# logic.net
KiCad netlist of a schematic drawn in Altium Designer
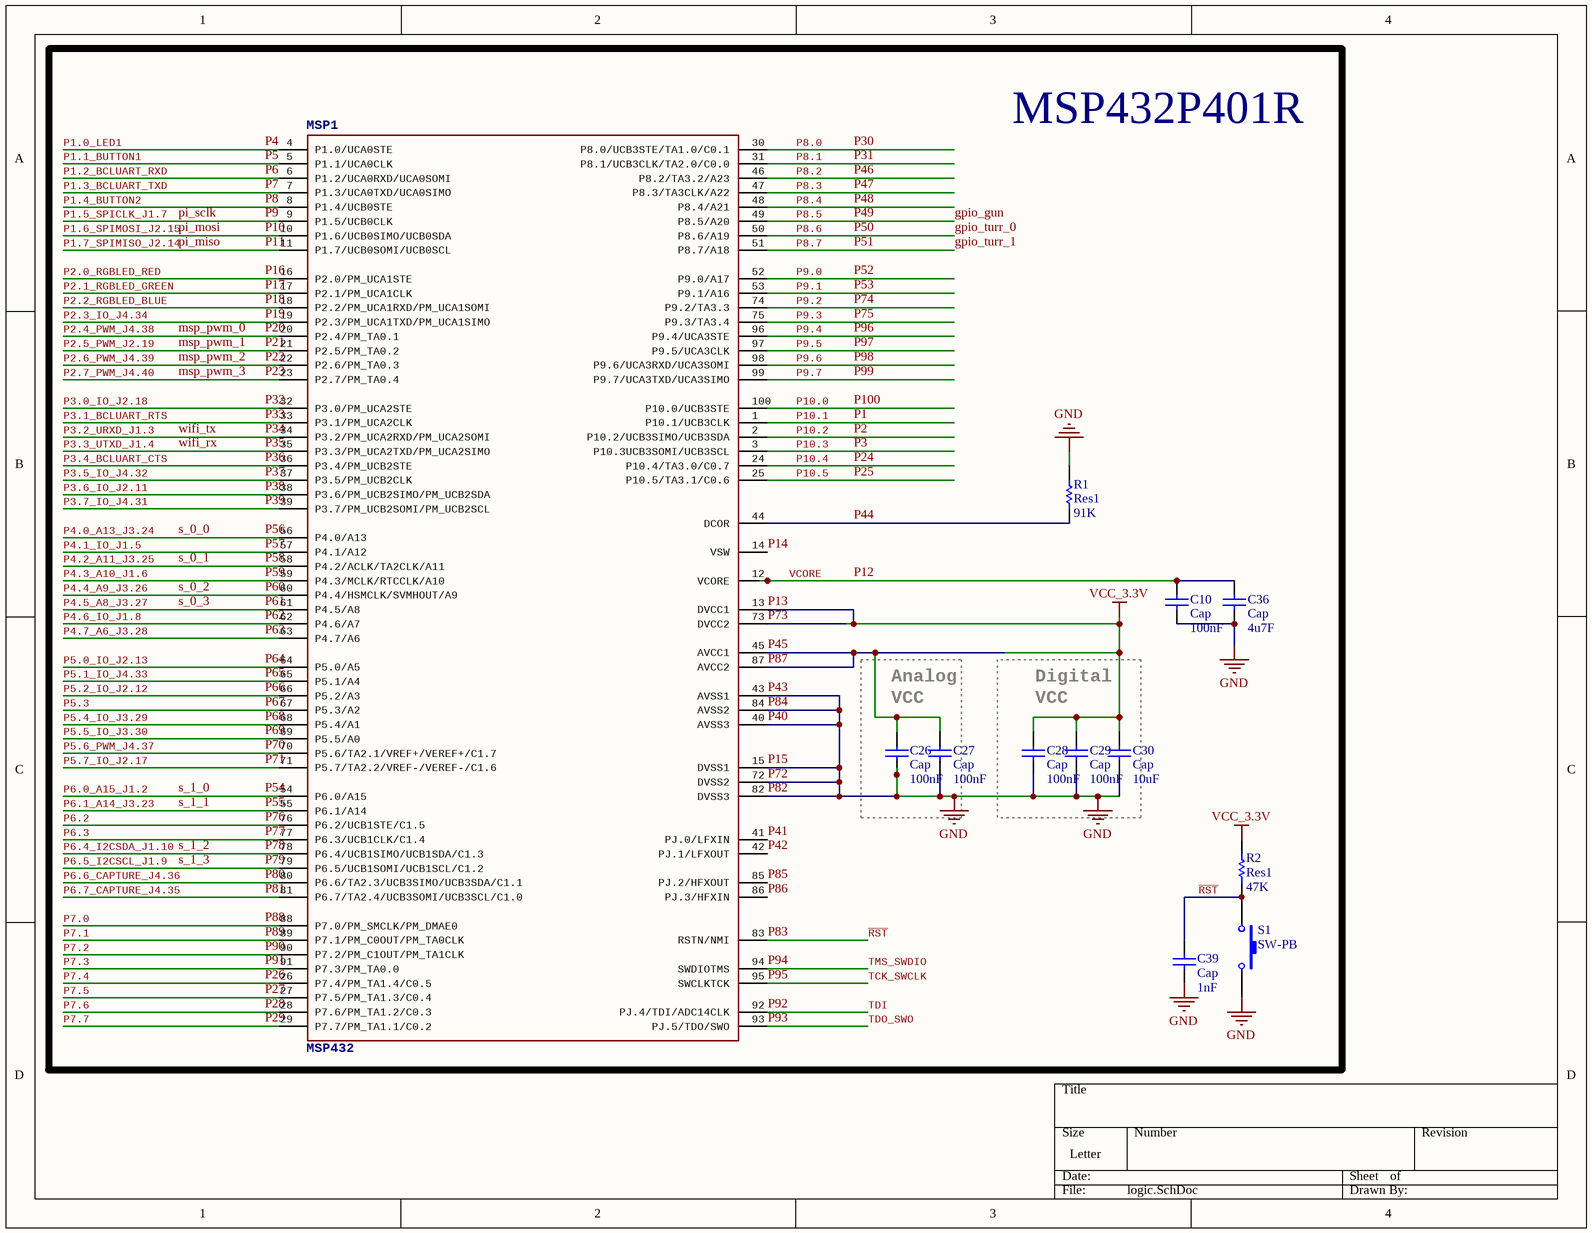
[diagram p0: logic.SchDoc]

(export (version "E")
  (design (tool "Eeschema 10.0.6"))
  (components
    (comp (ref "C10")
      (value "Cap")
      (footprint "RAD-0.1")
      (description "Capacitor")
      (fields (field (name "ALTIUM_VALUE") "100nF") (field (name "PUBLISHER") "Altium Limited"))
      (libsource (lib "Miscellaneous Devices") (part "Cap"))
    )
    (comp (ref "C26")
      (value "Cap")
      (footprint "RAD-0.1")
      (description "Capacitor")
      (fields (field (name "ALTIUM_VALUE") "100nF") (field (name "PUBLISHER") "Altium Limited"))
      (libsource (lib "Miscellaneous Devices") (part "Cap"))
    )
    (comp (ref "C27")
      (value "Cap")
      (footprint "RAD-0.1")
      (description "Capacitor")
      (fields (field (name "ALTIUM_VALUE") "100nF") (field (name "PUBLISHER") "Altium Limited"))
      (libsource (lib "Miscellaneous Devices") (part "Cap"))
    )
    (comp (ref "C28")
      (value "Cap")
      (footprint "RAD-0.1")
      (description "Capacitor")
      (fields (field (name "ALTIUM_VALUE") "100nF") (field (name "PUBLISHER") "Altium Limited"))
      (libsource (lib "Miscellaneous Devices") (part "Cap"))
    )
    (comp (ref "C29")
      (value "Cap")
      (footprint "RAD-0.1")
      (description "Capacitor")
      (fields (field (name "ALTIUM_VALUE") "100nF") (field (name "PUBLISHER") "Altium Limited"))
      (libsource (lib "Miscellaneous Devices") (part "Cap"))
    )
    (comp (ref "C30")
      (value "Cap")
      (footprint "RAD-0.1")
      (description "Capacitor")
      (fields (field (name "ALTIUM_VALUE") "10uF") (field (name "PUBLISHER") "Altium Limited"))
      (libsource (lib "Miscellaneous Devices") (part "Cap"))
    )
    (comp (ref "C36")
      (value "Cap")
      (footprint "RAD-0.1")
      (description "Capacitor")
      (fields (field (name "ALTIUM_VALUE") "4u7F") (field (name "PUBLISHER") "Altium Limited"))
      (libsource (lib "Miscellaneous Devices") (part "Cap"))
    )
    (comp (ref "C39")
      (value "Cap")
      (footprint "RAD-0.1")
      (description "Capacitor")
      (fields (field (name "ALTIUM_VALUE") "1nF") (field (name "PUBLISHER") "Altium Limited"))
      (libsource (lib "Miscellaneous Devices") (part "Cap"))
    )
    (comp (ref "MSP1") (value "MSP432") (footprint "PZ100_L") (libsource (lib "MSP-EXP432") (part "MSP432")))
    (comp (ref "R1")
      (value "Res1")
      (footprint "AXIAL-0.3")
      (description "Resistor")
      (fields (field (name "ALTIUM_VALUE") "91K") (field (name "PUBLISHER") "Altium Limited"))
      (libsource (lib "Miscellaneous Devices") (part "Res1"))
    )
    (comp (ref "R2")
      (value "Res1")
      (footprint "AXIAL-0.3")
      (description "Resistor")
      (fields (field (name "ALTIUM_VALUE") "47K") (field (name "PUBLISHER") "Altium Limited"))
      (libsource (lib "Miscellaneous Devices") (part "Res1"))
    )
    (comp (ref "S1")
      (value "SW-PB")
      (footprint "SW PB")
      (description "DIGIKEY SW400-ND")
      (fields (field (name "PUBLISHER") "Altium Limited"))
      (libsource (lib "ECE LIB new") (part "SW-PB_2"))
    )
  )
  (nets
    (net (code "1") (name "/P1") (class "Default")
      (node (ref "MSP1") (pin "1") (pinfunction "P10.1/UCB3CLK_1") (pintype "power_in"))
    )
    (net (code "2") (name "/P1.0_LED1") (class "Default")
      (node (ref "MSP1") (pin "4") (pinfunction "P1.0/UCA0STE_4") (pintype "power_in"))
    )
    (net (code "3") (name "/P1.1_BUTTON1") (class "Default")
      (node (ref "MSP1") (pin "5") (pinfunction "P1.1/UCA0CLK_5") (pintype "power_in"))
    )
    (net (code "4") (name "/P1.2_BCLUART_RXD") (class "Default")
      (node (ref "MSP1") (pin "6") (pinfunction "P1.2/UCA0RXD/UCA0SOMI_6") (pintype "power_in"))
    )
    (net (code "5") (name "/P1.3_BCLUART_TXD") (class "Default")
      (node (ref "MSP1") (pin "7") (pinfunction "P1.3/UCA0TXD/UCA0SIMO_7") (pintype "power_in"))
    )
    (net (code "6") (name "/P1.4_BUTTON2") (class "Default")
      (node (ref "MSP1") (pin "8") (pinfunction "P1.4/UCB0STE_8") (pintype "power_in"))
    )
    (net (code "7") (name "/P1.5_SPICLK_J1.7") (class "Default")
      (node (ref "MSP1") (pin "9") (pinfunction "P1.5/UCB0CLK_9") (pintype "power_in"))
    )
    (net (code "8") (name "/P1.6_SPIMOSI_J2.15") (class "Default")
      (node (ref "MSP1") (pin "10") (pinfunction "P1.6/UCB0SIMO/UCB0SDA_10") (pintype "power_in"))
    )
    (net (code "9") (name "/P1.7_SPIMISO_J2.14") (class "Default")
      (node (ref "MSP1") (pin "11") (pinfunction "P1.7/UCB0SOMI/UCB0SCL_11") (pintype "power_in"))
    )
    (net (code "10") (name "/P2.4_PWM_J4.38") (class "Default")
      (node (ref "MSP1") (pin "20") (pinfunction "P2.4/PM_TA0.1_20") (pintype "power_in"))
    )
    (net (code "11") (name "/P2.5_PWM_J2.19") (class "Default")
      (node (ref "MSP1") (pin "21") (pinfunction "P2.5/PM_TA0.2_21") (pintype "power_in"))
    )
    (net (code "12") (name "/P2.6_PWM_J4.39") (class "Default")
      (node (ref "MSP1") (pin "22") (pinfunction "P2.6/PM_TA0.3_22") (pintype "power_in"))
    )
    (net (code "13") (name "/P2.7_PWM_J4.40") (class "Default")
      (node (ref "MSP1") (pin "23") (pinfunction "P2.7/PM_TA0.4_23") (pintype "power_in"))
    )
    (net (code "14") (name "/P3.0_IO_J2.18") (class "Default")
      (node (ref "MSP1") (pin "32") (pinfunction "P3.0/PM_UCA2STE_32") (pintype "power_in"))
    )
    (net (code "15") (name "/P3.1_BCLUART_RTS") (class "Default")
      (node (ref "MSP1") (pin "33") (pinfunction "P3.1/PM_UCA2CLK_33") (pintype "power_in"))
    )
    (net (code "16") (name "/P3.2_URXD_J1.3") (class "Default")
      (node (ref "MSP1") (pin "34") (pinfunction "P3.2/PM_UCA2RXD/PM_UCA2SOMI_34") (pintype "power_in"))
    )
    (net (code "17") (name "/P3.3_UTXD_J1.4") (class "Default")
      (node (ref "MSP1") (pin "35") (pinfunction "P3.3/PM_UCA2TXD/PM_UCA2SIMO_35") (pintype "power_in"))
    )
    (net (code "18") (name "/P3.4_BCLUART_CTS") (class "Default")
      (node (ref "MSP1") (pin "36") (pinfunction "P3.4/PM_UCB2STE_36") (pintype "power_in"))
    )
    (net (code "19") (name "/P3.5_IO_J4.32") (class "Default")
      (node (ref "MSP1") (pin "37") (pinfunction "P3.5/PM_UCB2CLK_37") (pintype "power_in"))
    )
    (net (code "20") (name "/P3.6_IO_J2.11") (class "Default")
      (node (ref "MSP1") (pin "38") (pinfunction "P3.6/PM_UCB2SIMO/PM_UCB2SDA_38") (pintype "power_in"))
    )
    (net (code "21") (name "/P3.7_IO_J4.31") (class "Default")
      (node (ref "MSP1") (pin "39") (pinfunction "P3.7/PM_UCB2SOMI/PM_UCB2SCL_39") (pintype "power_in"))
    )
    (net (code "22") (name "/P4.0_A13_J3.24") (class "Default")
      (node (ref "MSP1") (pin "56") (pinfunction "P4.0/A13_56") (pintype "power_in"))
    )
    (net (code "23") (name "/P4.1_IO_J1.5") (class "Default")
      (node (ref "MSP1") (pin "57") (pinfunction "P4.1/A12_57") (pintype "power_in"))
    )
    (net (code "24") (name "/P4.2_A11_J3.25") (class "Default")
      (node (ref "MSP1") (pin "58") (pinfunction "P4.2/ACLK/TA2CLK/A11_58") (pintype "power_in"))
    )
    (net (code "25") (name "/P4.3_A10_J1.6") (class "Default")
      (node (ref "MSP1") (pin "59") (pinfunction "P4.3/MCLK/RTCCLK/A10_59") (pintype "power_in"))
    )
    (net (code "26") (name "/P4.4_A9_J3.26") (class "Default")
      (node (ref "MSP1") (pin "60") (pinfunction "P4.4/HSMCLK/SVMHOUT/A9_60") (pintype "power_in"))
    )
    (net (code "27") (name "/P4.5_A8_J3.27") (class "Default")
      (node (ref "MSP1") (pin "61") (pinfunction "P4.5/A8_61") (pintype "power_in"))
    )
    (net (code "28") (name "/P4.6_IO_J1.8") (class "Default")
      (node (ref "MSP1") (pin "62") (pinfunction "P4.6/A7_62") (pintype "power_in"))
    )
    (net (code "29") (name "/P4.7_A6_J3.28") (class "Default")
      (node (ref "MSP1") (pin "63") (pinfunction "P4.7/A6_63") (pintype "power_in"))
    )
    (net (code "30") (name "/P5.0_IO_J2.13") (class "Default")
      (node (ref "MSP1") (pin "64") (pinfunction "P5.0/A5_64") (pintype "power_in"))
    )
    (net (code "31") (name "/P5.1_IO_J4.33") (class "Default")
      (node (ref "MSP1") (pin "65") (pinfunction "P5.1/A4_65") (pintype "power_in"))
    )
    (net (code "32") (name "/P5.2_IO_J2.12") (class "Default")
      (node (ref "MSP1") (pin "66") (pinfunction "P5.2/A3_66") (pintype "power_in"))
    )
    (net (code "33") (name "/P5.3") (class "Default")
      (node (ref "MSP1") (pin "67") (pinfunction "P5.3/A2_67") (pintype "power_in"))
    )
    (net (code "34") (name "/P5.4_IO_J3.29") (class "Default")
      (node (ref "MSP1") (pin "68") (pinfunction "P5.4/A1_68") (pintype "power_in"))
    )
    (net (code "35") (name "/P5.5_IO_J3.30") (class "Default")
      (node (ref "MSP1") (pin "69") (pinfunction "P5.5/A0_69") (pintype "power_in"))
    )
    (net (code "36") (name "/P5.6_PWM_J4.37") (class "Default")
      (node (ref "MSP1") (pin "70") (pinfunction "P5.6/TA2.1/VREF+/VEREF+/C1.7_70") (pintype "power_in"))
    )
    (net (code "37") (name "/P5.7_IO_J2.17") (class "Default")
      (node (ref "MSP1") (pin "71") (pinfunction "P5.7/TA2.2/VREF-/VEREF-/C1.6_71") (pintype "power_in"))
    )
    (net (code "38") (name "/P6.2") (class "Default")
      (node (ref "MSP1") (pin "76") (pinfunction "P6.2/UCB1STE/C1.5_76") (pintype "power_in"))
    )
    (net (code "39") (name "/P6.3") (class "Default")
      (node (ref "MSP1") (pin "77") (pinfunction "P6.3/UCB1CLK/C1.4_77") (pintype "power_in"))
    )
    (net (code "40") (name "/P6.4_I2CSDA_J1.10") (class "Default")
      (node (ref "MSP1") (pin "78") (pinfunction "P6.4/UCB1SIMO/UCB1SDA/C1.3_78") (pintype "power_in"))
    )
    (net (code "41") (name "/P6.5_I2CSCL_J1.9") (class "Default")
      (node (ref "MSP1") (pin "79") (pinfunction "P6.5/UCB1SOMI/UCB1SCL/C1.2_79") (pintype "power_in"))
    )
    (net (code "42") (name "/P6.6_CAPTURE_J4.36") (class "Default")
      (node (ref "MSP1") (pin "80") (pinfunction "P6.6/TA2.3/UCB3SIMO/UCB3SDA/C1.1_80") (pintype "power_in"))
    )
    (net (code "43") (name "/P6.7_CAPTURE_J4.35") (class "Default")
      (node (ref "MSP1") (pin "81") (pinfunction "P6.7/TA2.4/UCB3SOMI/UCB3SCL/C1.0_81") (pintype "power_in"))
    )
    (net (code "44") (name "/P7.0") (class "Default")
      (node (ref "MSP1") (pin "88") (pinfunction "P7.0/PM_SMCLK/PM_DMAE0_88") (pintype "power_in"))
    )
    (net (code "45") (name "/P7.1") (class "Default")
      (node (ref "MSP1") (pin "89") (pinfunction "P7.1/PM_C0OUT/PM_TA0CLK_89") (pintype "power_in"))
    )
    (net (code "46") (name "/P7.2") (class "Default")
      (node (ref "MSP1") (pin "90") (pinfunction "P7.2/PM_C1OUT/PM_TA1CLK_90") (pintype "power_in"))
    )
    (net (code "47") (name "/P7.3") (class "Default")
      (node (ref "MSP1") (pin "91") (pinfunction "P7.3/PM_TA0.0_91") (pintype "power_in"))
    )
    (net (code "48") (name "/P9.4") (class "Default")
      (node (ref "MSP1") (pin "96") (pinfunction "P9.4/UCA3STE_96") (pintype "power_in"))
    )
    (net (code "49") (name "/P9.5") (class "Default")
      (node (ref "MSP1") (pin "97") (pinfunction "P9.5/UCA3CLK_97") (pintype "power_in"))
    )
    (net (code "50") (name "/P9.6") (class "Default")
      (node (ref "MSP1") (pin "98") (pinfunction "P9.6/UCA3RXD/UCA3SOMI_98") (pintype "power_in"))
    )
    (net (code "51") (name "/P9.7") (class "Default")
      (node (ref "MSP1") (pin "99") (pinfunction "P9.7/UCA3TXD/UCA3SIMO_99") (pintype "power_in"))
    )
    (net (code "52") (name "/P10.0") (class "Default")
      (node (ref "MSP1") (pin "100") (pinfunction "P10.0/UCB3STE_100") (pintype "power_in"))
    )
    (net (code "53") (name "/P10.2") (class "Default")
      (node (ref "MSP1") (pin "2") (pinfunction "P10.2/UCB3SIMO/UCB3SDA_2") (pintype "power_in"))
    )
    (net (code "54") (name "/P10.3") (class "Default")
      (node (ref "MSP1") (pin "3") (pinfunction "P10.3UCB3SOMI/UCB3SCL_3") (pintype "power_in"))
    )
    (net (code "55") (name "/P10.4") (class "Default")
      (node (ref "MSP1") (pin "24") (pinfunction "P10.4/TA3.0/C0.7_24") (pintype "power_in"))
    )
    (net (code "56") (name "/P10.5") (class "Default")
      (node (ref "MSP1") (pin "25") (pinfunction "P10.5/TA3.1/C0.6_25") (pintype "power_in"))
    )
    (net (code "57") (name "/P12") (class "Default")
      (node (ref "C10") (pin "2") (pinfunction "2_2") (pintype "passive"))
      (node (ref "C36") (pin "2") (pinfunction "2_2") (pintype "passive"))
      (node (ref "MSP1") (pin "12") (pinfunction "VCORE_12") (pintype "power_in"))
    )
    (net (code "58") (name "/P14") (class "Default")
      (node (ref "MSP1") (pin "14") (pinfunction "VSW_14") (pintype "power_in"))
    )
    (net (code "59") (name "/P16") (class "Default")
      (node (ref "MSP1") (pin "16") (pinfunction "P2.0/PM_UCA1STE_16") (pintype "power_in"))
    )
    (net (code "60") (name "/P17") (class "Default")
      (node (ref "MSP1") (pin "17") (pinfunction "P2.1/PM_UCA1CLK_17") (pintype "power_in"))
    )
    (net (code "61") (name "/P18") (class "Default")
      (node (ref "MSP1") (pin "18") (pinfunction "P2.2/PM_UCA1RXD/PM_UCA1SOMI_18") (pintype "power_in"))
    )
    (net (code "62") (name "/P19") (class "Default")
      (node (ref "MSP1") (pin "19") (pinfunction "P2.3/PM_UCA1TXD/PM_UCA1SIMO_19") (pintype "power_in"))
    )
    (net (code "63") (name "/P26") (class "Default")
      (node (ref "MSP1") (pin "26") (pinfunction "P7.4/PM_TA1.4/C0.5_26") (pintype "power_in"))
    )
    (net (code "64") (name "/P27") (class "Default")
      (node (ref "MSP1") (pin "27") (pinfunction "P7.5/PM_TA1.3/C0.4_27") (pintype "power_in"))
    )
    (net (code "65") (name "/P28") (class "Default")
      (node (ref "MSP1") (pin "28") (pinfunction "P7.6/PM_TA1.2/C0.3_28") (pintype "power_in"))
    )
    (net (code "66") (name "/P29") (class "Default")
      (node (ref "MSP1") (pin "29") (pinfunction "P7.7/PM_TA1.1/C0.2_29") (pintype "power_in"))
    )
    (net (code "67") (name "/P30") (class "Default")
      (node (ref "MSP1") (pin "30") (pinfunction "P8.0/UCB3STE/TA1.0/C0.1_30") (pintype "power_in"))
    )
    (net (code "68") (name "/P31") (class "Default")
      (node (ref "MSP1") (pin "31") (pinfunction "P8.1/UCB3CLK/TA2.0/C0.0_31") (pintype "power_in"))
    )
    (net (code "69") (name "/P41") (class "Default")
      (node (ref "MSP1") (pin "41") (pinfunction "PJ.0/LFXIN_41") (pintype "power_in"))
    )
    (net (code "70") (name "/P42") (class "Default")
      (node (ref "MSP1") (pin "42") (pinfunction "PJ.1/LFXOUT_42") (pintype "power_in"))
    )
    (net (code "71") (name "/P44") (class "Default")
      (node (ref "MSP1") (pin "44") (pinfunction "DCOR_44") (pintype "power_in"))
      (node (ref "R1") (pin "2") (pinfunction "2_2") (pintype "passive"))
    )
    (net (code "72") (name "/P46") (class "Default")
      (node (ref "MSP1") (pin "46") (pinfunction "P8.2/TA3.2/A23_46") (pintype "power_in"))
    )
    (net (code "73") (name "/P47") (class "Default")
      (node (ref "MSP1") (pin "47") (pinfunction "P8.3/TA3CLK/A22_47") (pintype "power_in"))
    )
    (net (code "74") (name "/P48") (class "Default")
      (node (ref "MSP1") (pin "48") (pinfunction "P8.4/A21_48") (pintype "power_in"))
    )
    (net (code "75") (name "/P49") (class "Default")
      (node (ref "MSP1") (pin "49") (pinfunction "P8.5/A20_49") (pintype "power_in"))
    )
    (net (code "76") (name "/P50") (class "Default")
      (node (ref "MSP1") (pin "50") (pinfunction "P8.6/A19_50") (pintype "power_in"))
    )
    (net (code "77") (name "/P51") (class "Default")
      (node (ref "MSP1") (pin "51") (pinfunction "P8.7/A18_51") (pintype "power_in"))
    )
    (net (code "78") (name "/P52") (class "Default")
      (node (ref "MSP1") (pin "52") (pinfunction "P9.0/A17_52") (pintype "power_in"))
    )
    (net (code "79") (name "/P53") (class "Default")
      (node (ref "MSP1") (pin "53") (pinfunction "P9.1/A16_53") (pintype "power_in"))
    )
    (net (code "80") (name "/P54") (class "Default")
      (node (ref "MSP1") (pin "54") (pinfunction "P6.0/A15_54") (pintype "power_in"))
    )
    (net (code "81") (name "/P55") (class "Default")
      (node (ref "MSP1") (pin "55") (pinfunction "P6.1/A14_55") (pintype "power_in"))
    )
    (net (code "82") (name "/P74") (class "Default")
      (node (ref "MSP1") (pin "74") (pinfunction "P9.2/TA3.3_74") (pintype "power_in"))
    )
    (net (code "83") (name "/P75") (class "Default")
      (node (ref "MSP1") (pin "75") (pinfunction "P9.3/TA3.4_75") (pintype "power_in"))
    )
    (net (code "84") (name "/P83") (class "Default")
      (node (ref "C39") (pin "2") (pinfunction "2_2") (pintype "passive"))
      (node (ref "MSP1") (pin "83") (pinfunction "RSTN/NMI_83") (pintype "power_in"))
      (node (ref "R2") (pin "1") (pinfunction "1_1") (pintype "passive"))
      (node (ref "S1") (pin "1") (pinfunction "1_1") (pintype "passive"))
    )
    (net (code "85") (name "/P85") (class "Default")
      (node (ref "MSP1") (pin "85") (pinfunction "PJ.2/HFXOUT_85") (pintype "power_in"))
    )
    (net (code "86") (name "/P86") (class "Default")
      (node (ref "MSP1") (pin "86") (pinfunction "PJ.3/HFXIN_86") (pintype "power_in"))
    )
    (net (code "87") (name "/P92") (class "Default")
      (node (ref "MSP1") (pin "92") (pinfunction "PJ.4/TDI/ADC14CLK_92") (pintype "power_in"))
    )
    (net (code "88") (name "/P93") (class "Default")
      (node (ref "MSP1") (pin "93") (pinfunction "PJ.5/TDO/SWO_93") (pintype "power_in"))
    )
    (net (code "89") (name "/P94") (class "Default")
      (node (ref "MSP1") (pin "94") (pinfunction "SWDIOTMS_94") (pintype "power_in"))
    )
    (net (code "90") (name "/P95") (class "Default")
      (node (ref "MSP1") (pin "95") (pinfunction "SWCLKTCK_95") (pintype "power_in"))
    )
    (net (code "91") (name "GND") (class "Default")
      (node (ref "C10") (pin "1") (pinfunction "1_1") (pintype "passive"))
      (node (ref "C26") (pin "1") (pinfunction "1_1") (pintype "passive"))
      (node (ref "C27") (pin "1") (pinfunction "1_1") (pintype "passive"))
      (node (ref "C28") (pin "1") (pinfunction "1_1") (pintype "passive"))
      (node (ref "C29") (pin "1") (pinfunction "1_1") (pintype "passive"))
      (node (ref "C30") (pin "1") (pinfunction "1_1") (pintype "passive"))
      (node (ref "C36") (pin "1") (pinfunction "1_1") (pintype "passive"))
      (node (ref "C39") (pin "1") (pinfunction "1_1") (pintype "passive"))
      (node (ref "MSP1") (pin "15") (pinfunction "DVSS1_15") (pintype "power_in"))
      (node (ref "MSP1") (pin "40") (pinfunction "AVSS3_40") (pintype "power_in"))
      (node (ref "MSP1") (pin "43") (pinfunction "AVSS1_43") (pintype "power_in"))
      (node (ref "MSP1") (pin "72") (pinfunction "DVSS2_72") (pintype "power_in"))
      (node (ref "MSP1") (pin "82") (pinfunction "DVSS3_82") (pintype "power_in"))
      (node (ref "MSP1") (pin "84") (pinfunction "AVSS2_84") (pintype "power_in"))
      (node (ref "R1") (pin "1") (pinfunction "1_1") (pintype "passive"))
      (node (ref "S1") (pin "2") (pinfunction "2_2") (pintype "passive"))
    )
    (net (code "92") (name "VCC_3.3V") (class "Default")
      (node (ref "C26") (pin "2") (pinfunction "2_2") (pintype "passive"))
      (node (ref "C27") (pin "2") (pinfunction "2_2") (pintype "passive"))
      (node (ref "C28") (pin "2") (pinfunction "2_2") (pintype "passive"))
      (node (ref "C29") (pin "2") (pinfunction "2_2") (pintype "passive"))
      (node (ref "C30") (pin "2") (pinfunction "2_2") (pintype "passive"))
      (node (ref "MSP1") (pin "13") (pinfunction "DVCC1_13") (pintype "power_in"))
      (node (ref "MSP1") (pin "45") (pinfunction "AVCC1_45") (pintype "power_in"))
      (node (ref "MSP1") (pin "73") (pinfunction "DVCC2_73") (pintype "power_in"))
      (node (ref "MSP1") (pin "87") (pinfunction "AVCC2_87") (pintype "power_in"))
      (node (ref "R2") (pin "2") (pinfunction "2_2") (pintype "passive"))
    )
  )
)
